# TouchMyHeart.net
KiCad netlist of a schematic drawn in Altium Designer
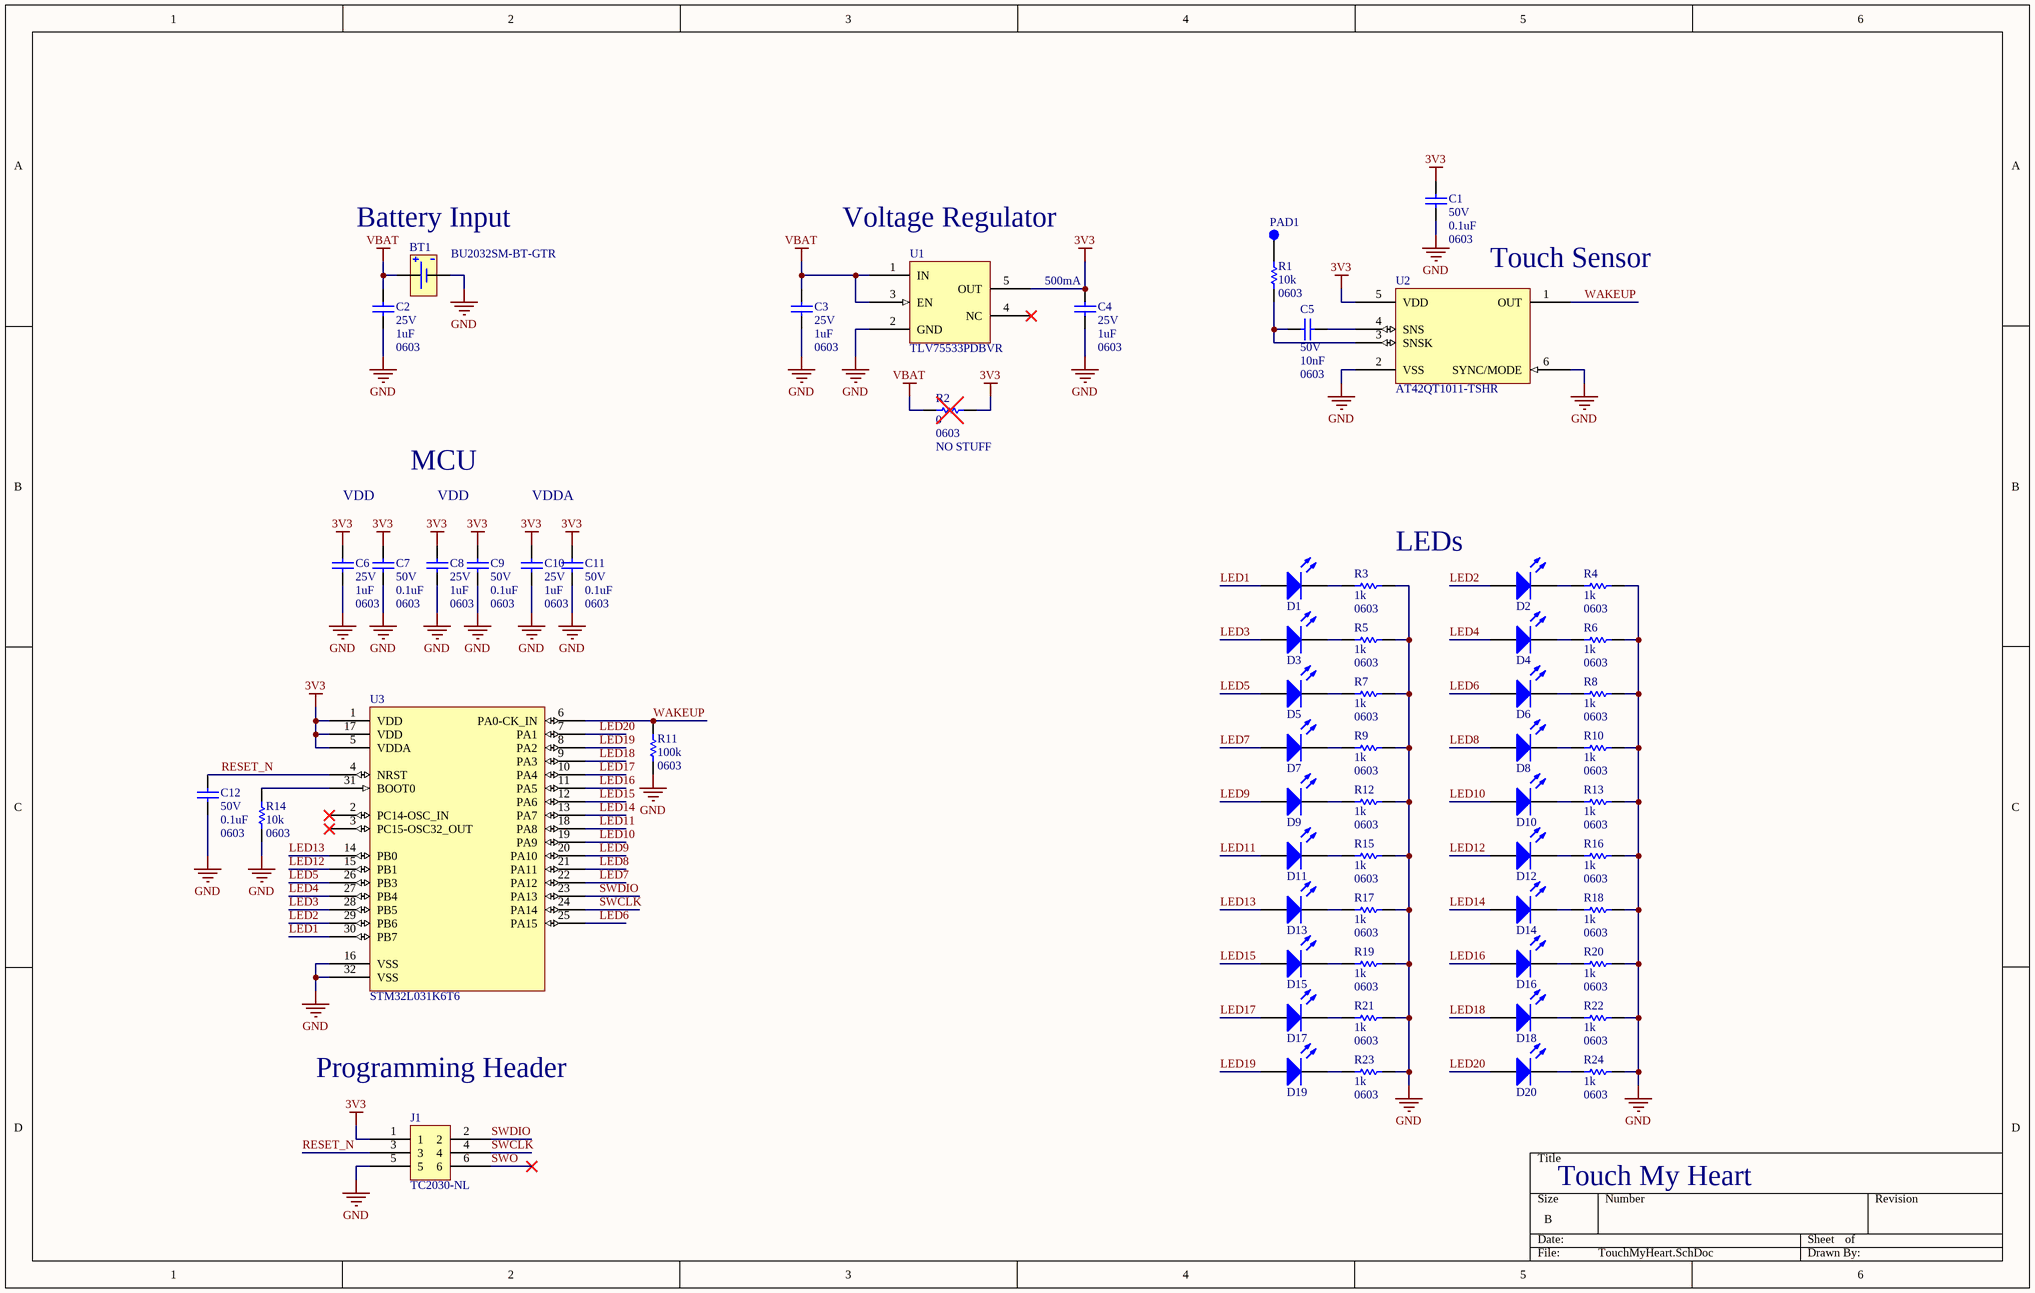
[diagram p0: TouchMyHeart.SchDoc]

(export (version "E")
  (design (tool "Eeschema 10.0.6"))
  (components
    (comp (ref "BT1")
      (value "BU2032SM-BT-GTR")
      (footprint "Footprint_Battery:BU2032SM-BT-GTR")
      (description "BATTERY HOLDER COIN 20MM SMD")
      (fields (field (name "MANUFACTURER") "Memory Protection Devices"))
      (libsource (lib "Schematic_Battery") (part "BU2032SM-BT-GTR"))
    )
    (comp (ref "C1")
      (value "0.1uF")
      (footprint "Footprint_Capacitor:CAPC1608X09N")
      (description "General purpose capacitor")
      (fields
        (field (name "RATED VOLTAGE") "50V")
        (field (name "PACKAGE") "0603")
        (field (name "Comment") "Capacitor")
      )
      (libsource (lib "Schematic_Generic") (part "Capacitor"))
    )
    (comp (ref "C2")
      (value "1uF")
      (footprint "Footprint_Capacitor:CAPC1608X09N")
      (description "General purpose capacitor")
      (fields
        (field (name "RATED VOLTAGE") "25V")
        (field (name "PACKAGE") "0603")
        (field (name "Comment") "Capacitor")
      )
      (libsource (lib "Schematic_Generic") (part "Capacitor"))
    )
    (comp (ref "C3")
      (value "1uF")
      (footprint "Footprint_Capacitor:CAPC1608X09N")
      (description "General purpose capacitor")
      (fields
        (field (name "RATED VOLTAGE") "25V")
        (field (name "PACKAGE") "0603")
        (field (name "Comment") "Capacitor")
      )
      (libsource (lib "Schematic_Generic") (part "Capacitor"))
    )
    (comp (ref "C4")
      (value "1uF")
      (footprint "Footprint_Capacitor:CAPC1608X09N")
      (description "General purpose capacitor")
      (fields
        (field (name "RATED VOLTAGE") "25V")
        (field (name "PACKAGE") "0603")
        (field (name "Comment") "Capacitor")
      )
      (libsource (lib "Schematic_Generic") (part "Capacitor"))
    )
    (comp (ref "C5")
      (value "10nF")
      (footprint "Footprint_Capacitor:CAPC1608X09N")
      (description "General purpose capacitor")
      (fields
        (field (name "RATED VOLTAGE") "50V")
        (field (name "PACKAGE") "0603")
        (field (name "Comment") "Capacitor")
      )
      (libsource (lib "Schematic_Generic") (part "Capacitor"))
    )
    (comp (ref "C6")
      (value "1uF")
      (footprint "Footprint_Capacitor:CAPC1608X09N")
      (description "General purpose capacitor")
      (fields
        (field (name "RATED VOLTAGE") "25V")
        (field (name "PACKAGE") "0603")
        (field (name "Comment") "Capacitor")
      )
      (libsource (lib "Schematic_Generic") (part "Capacitor"))
    )
    (comp (ref "C7")
      (value "0.1uF")
      (footprint "Footprint_Capacitor:CAPC1608X09N")
      (description "General purpose capacitor")
      (fields
        (field (name "RATED VOLTAGE") "50V")
        (field (name "PACKAGE") "0603")
        (field (name "Comment") "Capacitor")
      )
      (libsource (lib "Schematic_Generic") (part "Capacitor"))
    )
    (comp (ref "C8")
      (value "1uF")
      (footprint "Footprint_Capacitor:CAPC1608X09N")
      (description "General purpose capacitor")
      (fields
        (field (name "RATED VOLTAGE") "25V")
        (field (name "PACKAGE") "0603")
        (field (name "Comment") "Capacitor")
      )
      (libsource (lib "Schematic_Generic") (part "Capacitor"))
    )
    (comp (ref "C9")
      (value "0.1uF")
      (footprint "Footprint_Capacitor:CAPC1608X09N")
      (description "General purpose capacitor")
      (fields
        (field (name "RATED VOLTAGE") "50V")
        (field (name "PACKAGE") "0603")
        (field (name "Comment") "Capacitor")
      )
      (libsource (lib "Schematic_Generic") (part "Capacitor"))
    )
    (comp (ref "C10")
      (value "1uF")
      (footprint "Footprint_Capacitor:CAPC1608X09N")
      (description "General purpose capacitor")
      (fields
        (field (name "RATED VOLTAGE") "25V")
        (field (name "PACKAGE") "0603")
        (field (name "Comment") "Capacitor")
      )
      (libsource (lib "Schematic_Generic") (part "Capacitor"))
    )
    (comp (ref "C11")
      (value "0.1uF")
      (footprint "Footprint_Capacitor:CAPC1608X09N")
      (description "General purpose capacitor")
      (fields
        (field (name "RATED VOLTAGE") "50V")
        (field (name "PACKAGE") "0603")
        (field (name "Comment") "Capacitor")
      )
      (libsource (lib "Schematic_Generic") (part "Capacitor"))
    )
    (comp (ref "C12")
      (value "0.1uF")
      (footprint "Footprint_Capacitor:CAPC1608X09N")
      (description "General purpose capacitor")
      (fields
        (field (name "RATED VOLTAGE") "50V")
        (field (name "PACKAGE") "0603")
        (field (name "Comment") "Capacitor")
      )
      (libsource (lib "Schematic_Generic") (part "Capacitor"))
    )
    (comp (ref "D1")
      (value "LED")
      (footprint "Footprint_LED:DIOC3216X11N")
      (description "General purpose LED")
      (libsource (lib "Schematic_Generic") (part "LED"))
    )
    (comp (ref "D2")
      (value "LED")
      (footprint "Footprint_LED:DIOC3216X11N")
      (description "General purpose LED")
      (libsource (lib "Schematic_Generic") (part "LED"))
    )
    (comp (ref "D3")
      (value "LED")
      (footprint "Footprint_LED:DIOC3216X11N")
      (description "General purpose LED")
      (libsource (lib "Schematic_Generic") (part "LED"))
    )
    (comp (ref "D4")
      (value "LED")
      (footprint "Footprint_LED:DIOC3216X11N")
      (description "General purpose LED")
      (libsource (lib "Schematic_Generic") (part "LED"))
    )
    (comp (ref "D5")
      (value "LED")
      (footprint "Footprint_LED:DIOC3216X11N")
      (description "General purpose LED")
      (libsource (lib "Schematic_Generic") (part "LED"))
    )
    (comp (ref "D6")
      (value "LED")
      (footprint "Footprint_LED:DIOC3216X11N")
      (description "General purpose LED")
      (libsource (lib "Schematic_Generic") (part "LED"))
    )
    (comp (ref "D7")
      (value "LED")
      (footprint "Footprint_LED:DIOC3216X11N")
      (description "General purpose LED")
      (libsource (lib "Schematic_Generic") (part "LED"))
    )
    (comp (ref "D8")
      (value "LED")
      (footprint "Footprint_LED:DIOC3216X11N")
      (description "General purpose LED")
      (libsource (lib "Schematic_Generic") (part "LED"))
    )
    (comp (ref "D9")
      (value "LED")
      (footprint "Footprint_LED:DIOC3216X11N")
      (description "General purpose LED")
      (libsource (lib "Schematic_Generic") (part "LED"))
    )
    (comp (ref "D10")
      (value "LED")
      (footprint "Footprint_LED:DIOC3216X11N")
      (description "General purpose LED")
      (libsource (lib "Schematic_Generic") (part "LED"))
    )
    (comp (ref "D11")
      (value "LED")
      (footprint "Footprint_LED:DIOC3216X11N")
      (description "General purpose LED")
      (libsource (lib "Schematic_Generic") (part "LED"))
    )
    (comp (ref "D12")
      (value "LED")
      (footprint "Footprint_LED:DIOC3216X11N")
      (description "General purpose LED")
      (libsource (lib "Schematic_Generic") (part "LED"))
    )
    (comp (ref "D13")
      (value "LED")
      (footprint "Footprint_LED:DIOC3216X11N")
      (description "General purpose LED")
      (libsource (lib "Schematic_Generic") (part "LED"))
    )
    (comp (ref "D14")
      (value "LED")
      (footprint "Footprint_LED:DIOC3216X11N")
      (description "General purpose LED")
      (libsource (lib "Schematic_Generic") (part "LED"))
    )
    (comp (ref "D15")
      (value "LED")
      (footprint "Footprint_LED:DIOC3216X11N")
      (description "General purpose LED")
      (libsource (lib "Schematic_Generic") (part "LED"))
    )
    (comp (ref "D16")
      (value "LED")
      (footprint "Footprint_LED:DIOC3216X11N")
      (description "General purpose LED")
      (libsource (lib "Schematic_Generic") (part "LED"))
    )
    (comp (ref "D17")
      (value "LED")
      (footprint "Footprint_LED:DIOC3216X11N")
      (description "General purpose LED")
      (libsource (lib "Schematic_Generic") (part "LED"))
    )
    (comp (ref "D18")
      (value "LED")
      (footprint "Footprint_LED:DIOC3216X11N")
      (description "General purpose LED")
      (libsource (lib "Schematic_Generic") (part "LED"))
    )
    (comp (ref "D19")
      (value "LED")
      (footprint "Footprint_LED:DIOC3216X11N")
      (description "General purpose LED")
      (libsource (lib "Schematic_Generic") (part "LED"))
    )
    (comp (ref "D20")
      (value "LED")
      (footprint "Footprint_LED:DIOC3216X11N")
      (description "General purpose LED")
      (libsource (lib "Schematic_Generic") (part "LED"))
    )
    (comp (ref "J1")
      (value "TC2030-NL")
      (footprint "Footprint_Connector:TC2030-NL")
      (description "6-Pin No-Legs Tag-Connect Plug-of-Nails™ Cable with Ribbon Connector")
      (libsource (lib "Schematic_Connector") (part "TC2030-NL"))
    )
    (comp (ref "PAD1")
      (value "~")
      (footprint "Footprint_Button:CAPACTIVE_TOUCH")
      (description "Capacitive Touch Button")
      (libsource (lib "Schematic_Button") (part "CAPACITIVE_TOUCH"))
    )
    (comp (ref "R1")
      (value "10k")
      (footprint "Footprint_Resistor:RESC1608X06N")
      (description "General purpose resistor")
      (fields (field (name "PACKAGE") "0603") (field (name "Comment") "Resistor"))
      (libsource (lib "Schematic_Generic") (part "Resistor"))
    )
    (comp (ref "R2")
      (value "0")
      (footprint "Footprint_Resistor:RESC1608X06N")
      (description "General purpose resistor")
      (fields
        (field (name "PACKAGE") "0603")
        (field (name "NOTE") "NO STUFF")
        (field (name "Comment") "Resistor")
      )
      (libsource (lib "Schematic_Generic") (part "Resistor"))
    )
    (comp (ref "R3")
      (value "1k")
      (footprint "Footprint_Resistor:RESC1608X06N")
      (description "General purpose resistor")
      (fields (field (name "PACKAGE") "0603") (field (name "Comment") "Resistor"))
      (libsource (lib "Schematic_Generic") (part "Resistor"))
    )
    (comp (ref "R4")
      (value "1k")
      (footprint "Footprint_Resistor:RESC1608X06N")
      (description "General purpose resistor")
      (fields (field (name "PACKAGE") "0603") (field (name "Comment") "Resistor"))
      (libsource (lib "Schematic_Generic") (part "Resistor"))
    )
    (comp (ref "R5")
      (value "1k")
      (footprint "Footprint_Resistor:RESC1608X06N")
      (description "General purpose resistor")
      (fields (field (name "PACKAGE") "0603") (field (name "Comment") "Resistor"))
      (libsource (lib "Schematic_Generic") (part "Resistor"))
    )
    (comp (ref "R6")
      (value "1k")
      (footprint "Footprint_Resistor:RESC1608X06N")
      (description "General purpose resistor")
      (fields (field (name "PACKAGE") "0603") (field (name "Comment") "Resistor"))
      (libsource (lib "Schematic_Generic") (part "Resistor"))
    )
    (comp (ref "R7")
      (value "1k")
      (footprint "Footprint_Resistor:RESC1608X06N")
      (description "General purpose resistor")
      (fields (field (name "PACKAGE") "0603") (field (name "Comment") "Resistor"))
      (libsource (lib "Schematic_Generic") (part "Resistor"))
    )
    (comp (ref "R8")
      (value "1k")
      (footprint "Footprint_Resistor:RESC1608X06N")
      (description "General purpose resistor")
      (fields (field (name "PACKAGE") "0603") (field (name "Comment") "Resistor"))
      (libsource (lib "Schematic_Generic") (part "Resistor"))
    )
    (comp (ref "R9")
      (value "1k")
      (footprint "Footprint_Resistor:RESC1608X06N")
      (description "General purpose resistor")
      (fields (field (name "PACKAGE") "0603") (field (name "Comment") "Resistor"))
      (libsource (lib "Schematic_Generic") (part "Resistor"))
    )
    (comp (ref "R10")
      (value "1k")
      (footprint "Footprint_Resistor:RESC1608X06N")
      (description "General purpose resistor")
      (fields (field (name "PACKAGE") "0603") (field (name "Comment") "Resistor"))
      (libsource (lib "Schematic_Generic") (part "Resistor"))
    )
    (comp (ref "R11")
      (value "100k")
      (footprint "Footprint_Resistor:RESC1608X06N")
      (description "General purpose resistor")
      (fields (field (name "PACKAGE") "0603") (field (name "Comment") "Resistor"))
      (libsource (lib "Schematic_Generic") (part "Resistor"))
    )
    (comp (ref "R12")
      (value "1k")
      (footprint "Footprint_Resistor:RESC1608X06N")
      (description "General purpose resistor")
      (fields (field (name "PACKAGE") "0603") (field (name "Comment") "Resistor"))
      (libsource (lib "Schematic_Generic") (part "Resistor"))
    )
    (comp (ref "R13")
      (value "1k")
      (footprint "Footprint_Resistor:RESC1608X06N")
      (description "General purpose resistor")
      (fields (field (name "PACKAGE") "0603") (field (name "Comment") "Resistor"))
      (libsource (lib "Schematic_Generic") (part "Resistor"))
    )
    (comp (ref "R14")
      (value "10k")
      (footprint "Footprint_Resistor:RESC1608X06N")
      (description "General purpose resistor")
      (fields (field (name "PACKAGE") "0603") (field (name "Comment") "Resistor"))
      (libsource (lib "Schematic_Generic") (part "Resistor"))
    )
    (comp (ref "R15")
      (value "1k")
      (footprint "Footprint_Resistor:RESC1608X06N")
      (description "General purpose resistor")
      (fields (field (name "PACKAGE") "0603") (field (name "Comment") "Resistor"))
      (libsource (lib "Schematic_Generic") (part "Resistor"))
    )
    (comp (ref "R16")
      (value "1k")
      (footprint "Footprint_Resistor:RESC1608X06N")
      (description "General purpose resistor")
      (fields (field (name "PACKAGE") "0603") (field (name "Comment") "Resistor"))
      (libsource (lib "Schematic_Generic") (part "Resistor"))
    )
    (comp (ref "R17")
      (value "1k")
      (footprint "Footprint_Resistor:RESC1608X06N")
      (description "General purpose resistor")
      (fields (field (name "PACKAGE") "0603") (field (name "Comment") "Resistor"))
      (libsource (lib "Schematic_Generic") (part "Resistor"))
    )
    (comp (ref "R18")
      (value "1k")
      (footprint "Footprint_Resistor:RESC1608X06N")
      (description "General purpose resistor")
      (fields (field (name "PACKAGE") "0603") (field (name "Comment") "Resistor"))
      (libsource (lib "Schematic_Generic") (part "Resistor"))
    )
    (comp (ref "R19")
      (value "1k")
      (footprint "Footprint_Resistor:RESC1608X06N")
      (description "General purpose resistor")
      (fields (field (name "PACKAGE") "0603") (field (name "Comment") "Resistor"))
      (libsource (lib "Schematic_Generic") (part "Resistor"))
    )
    (comp (ref "R20")
      (value "1k")
      (footprint "Footprint_Resistor:RESC1608X06N")
      (description "General purpose resistor")
      (fields (field (name "PACKAGE") "0603") (field (name "Comment") "Resistor"))
      (libsource (lib "Schematic_Generic") (part "Resistor"))
    )
    (comp (ref "R21")
      (value "1k")
      (footprint "Footprint_Resistor:RESC1608X06N")
      (description "General purpose resistor")
      (fields (field (name "PACKAGE") "0603") (field (name "Comment") "Resistor"))
      (libsource (lib "Schematic_Generic") (part "Resistor"))
    )
    (comp (ref "R22")
      (value "1k")
      (footprint "Footprint_Resistor:RESC1608X06N")
      (description "General purpose resistor")
      (fields (field (name "PACKAGE") "0603") (field (name "Comment") "Resistor"))
      (libsource (lib "Schematic_Generic") (part "Resistor"))
    )
    (comp (ref "R23")
      (value "1k")
      (footprint "Footprint_Resistor:RESC1608X06N")
      (description "General purpose resistor")
      (fields (field (name "PACKAGE") "0603") (field (name "Comment") "Resistor"))
      (libsource (lib "Schematic_Generic") (part "Resistor"))
    )
    (comp (ref "R24")
      (value "1k")
      (footprint "Footprint_Resistor:RESC1608X06N")
      (description "General purpose resistor")
      (fields (field (name "PACKAGE") "0603") (field (name "Comment") "Resistor"))
      (libsource (lib "Schematic_Generic") (part "Resistor"))
    )
    (comp (ref "U1")
      (value "TLV75533PDBVR")
      (footprint "Footprint_PMIC:SOT95P280X145-5N")
      (description "IC REG LINEAR 3.3V 500MA SOT23-5")
      (fields (field (name "MANUFACTURER") "Texas Instruments"))
      (libsource (lib "Schematic_PMIC") (part "TLV75533PDBVR"))
    )
    (comp (ref "U2")
      (value "AT42QT1011-TSHR")
      (footprint "Footprint_IC:SOT95P280X145-6N")
      (description "Touch Sensor IC 6-Pin SOT-23, HOLD")
      (fields (field (name "MANUFACTURER") "Microchip / Atmel"))
      (libsource (lib "Schematic_IC") (part "AT42QT1011-TSHR"))
    )
    (comp (ref "U3")
      (value "STM32L031K6T6")
      (footprint "Footprint_MCU:TQFP80P900X900X160-32N")
      (description "IC MCU 32BIT 32KB FLASH 32LQFP")
      (fields (field (name "MANUFACTURER") "STMicroelectronics"))
      (libsource (lib "Schematic_MCU") (part "STM32L031K6T6"))
    )
  )
  (nets
    (net (code "1") (name "/LED1") (class "Default")
      (node (ref "D1") (pin "1") (pinfunction "A_1") (pintype "passive"))
      (node (ref "U3") (pin "30") (pinfunction "PB7_30") (pintype "bidirectional"))
    )
    (net (code "2") (name "/LED2") (class "Default")
      (node (ref "D2") (pin "1") (pinfunction "A_1") (pintype "passive"))
      (node (ref "U3") (pin "29") (pinfunction "PB6_29") (pintype "bidirectional"))
    )
    (net (code "3") (name "/LED3") (class "Default")
      (node (ref "D3") (pin "1") (pinfunction "A_1") (pintype "passive"))
      (node (ref "U3") (pin "28") (pinfunction "PB5_28") (pintype "bidirectional"))
    )
    (net (code "4") (name "/LED4") (class "Default")
      (node (ref "D4") (pin "1") (pinfunction "A_1") (pintype "passive"))
      (node (ref "U3") (pin "27") (pinfunction "PB4_27") (pintype "bidirectional"))
    )
    (net (code "5") (name "/LED5") (class "Default")
      (node (ref "D5") (pin "1") (pinfunction "A_1") (pintype "passive"))
      (node (ref "U3") (pin "26") (pinfunction "PB3_26") (pintype "bidirectional"))
    )
    (net (code "6") (name "/LED6") (class "Default")
      (node (ref "D6") (pin "1") (pinfunction "A_1") (pintype "passive"))
      (node (ref "U3") (pin "25") (pinfunction "PA15_25") (pintype "bidirectional"))
    )
    (net (code "7") (name "/LED7") (class "Default")
      (node (ref "D7") (pin "1") (pinfunction "A_1") (pintype "passive"))
      (node (ref "U3") (pin "22") (pinfunction "PA12_22") (pintype "bidirectional"))
    )
    (net (code "8") (name "/LED8") (class "Default")
      (node (ref "D8") (pin "1") (pinfunction "A_1") (pintype "passive"))
      (node (ref "U3") (pin "21") (pinfunction "PA11_21") (pintype "bidirectional"))
    )
    (net (code "9") (name "/LED9") (class "Default")
      (node (ref "D9") (pin "1") (pinfunction "A_1") (pintype "passive"))
      (node (ref "U3") (pin "20") (pinfunction "PA10_20") (pintype "bidirectional"))
    )
    (net (code "10") (name "/LED10") (class "Default")
      (node (ref "D10") (pin "1") (pinfunction "A_1") (pintype "passive"))
      (node (ref "U3") (pin "19") (pinfunction "PA9_19") (pintype "bidirectional"))
    )
    (net (code "11") (name "/LED11") (class "Default")
      (node (ref "D11") (pin "1") (pinfunction "A_1") (pintype "passive"))
      (node (ref "U3") (pin "18") (pinfunction "PA8_18") (pintype "bidirectional"))
    )
    (net (code "12") (name "/LED12") (class "Default")
      (node (ref "D12") (pin "1") (pinfunction "A_1") (pintype "passive"))
      (node (ref "U3") (pin "15") (pinfunction "PB1_15") (pintype "bidirectional"))
    )
    (net (code "13") (name "/LED13") (class "Default")
      (node (ref "D13") (pin "1") (pinfunction "A_1") (pintype "passive"))
      (node (ref "U3") (pin "14") (pinfunction "PB0_14") (pintype "bidirectional"))
    )
    (net (code "14") (name "/LED14") (class "Default")
      (node (ref "D14") (pin "1") (pinfunction "A_1") (pintype "passive"))
      (node (ref "U3") (pin "13") (pinfunction "PA7_13") (pintype "bidirectional"))
    )
    (net (code "15") (name "/LED15") (class "Default")
      (node (ref "D15") (pin "1") (pinfunction "A_1") (pintype "passive"))
      (node (ref "U3") (pin "12") (pinfunction "PA6_12") (pintype "bidirectional"))
    )
    (net (code "16") (name "/LED16") (class "Default")
      (node (ref "D16") (pin "1") (pinfunction "A_1") (pintype "passive"))
      (node (ref "U3") (pin "11") (pinfunction "PA5_11") (pintype "bidirectional"))
    )
    (net (code "17") (name "/LED17") (class "Default")
      (node (ref "D17") (pin "1") (pinfunction "A_1") (pintype "passive"))
      (node (ref "U3") (pin "10") (pinfunction "PA4_10") (pintype "bidirectional"))
    )
    (net (code "18") (name "/LED18") (class "Default")
      (node (ref "D18") (pin "1") (pinfunction "A_1") (pintype "passive"))
      (node (ref "U3") (pin "9") (pinfunction "PA3_9") (pintype "bidirectional"))
    )
    (net (code "19") (name "/LED19") (class "Default")
      (node (ref "D19") (pin "1") (pinfunction "A_1") (pintype "passive"))
      (node (ref "U3") (pin "8") (pinfunction "PA2_8") (pintype "bidirectional"))
    )
    (net (code "20") (name "/LED20") (class "Default")
      (node (ref "D20") (pin "1") (pinfunction "A_1") (pintype "passive"))
      (node (ref "U3") (pin "7") (pinfunction "PA1_7") (pintype "bidirectional"))
    )
    (net (code "21") (name "/RESET_N") (class "Default")
      (node (ref "C12") (pin "2") (pinfunction "2_2") (pintype "passive"))
      (node (ref "J1") (pin "3") (pinfunction "3_3") (pintype "passive"))
      (node (ref "U3") (pin "4") (pinfunction "NRST_4") (pintype "bidirectional"))
    )
    (net (code "22") (name "/SWCLK") (class "Default")
      (node (ref "J1") (pin "4") (pinfunction "4_4") (pintype "passive"))
      (node (ref "U3") (pin "24") (pinfunction "PA14_24") (pintype "bidirectional"))
    )
    (net (code "23") (name "/SWDIO") (class "Default")
      (node (ref "J1") (pin "2") (pinfunction "2_2") (pintype "passive"))
      (node (ref "U3") (pin "23") (pinfunction "PA13_23") (pintype "bidirectional"))
    )
    (net (code "24") (name "/SWO") (class "Default")
      (node (ref "J1") (pin "6") (pinfunction "6_6") (pintype "passive+no_connect"))
    )
    (net (code "25") (name "/WAKEUP") (class "Default")
      (node (ref "R11") (pin "2") (pinfunction "2_2") (pintype "passive"))
      (node (ref "U2") (pin "1") (pinfunction "OUT_1") (pintype "power_in"))
      (node (ref "U3") (pin "6") (pinfunction "PA0-CK_IN_6") (pintype "bidirectional"))
    )
    (net (code "26") (name "3V3") (class "Default")
      (node (ref "C1") (pin "2") (pinfunction "2_2") (pintype "passive"))
      (node (ref "C10") (pin "2") (pinfunction "2_2") (pintype "passive"))
      (node (ref "C11") (pin "2") (pinfunction "2_2") (pintype "passive"))
      (node (ref "C4") (pin "2") (pinfunction "2_2") (pintype "passive"))
      (node (ref "C6") (pin "2") (pinfunction "2_2") (pintype "passive"))
      (node (ref "C7") (pin "2") (pinfunction "2_2") (pintype "passive"))
      (node (ref "C8") (pin "2") (pinfunction "2_2") (pintype "passive"))
      (node (ref "C9") (pin "2") (pinfunction "2_2") (pintype "passive"))
      (node (ref "J1") (pin "1") (pinfunction "1_1") (pintype "passive"))
      (node (ref "R2") (pin "1") (pinfunction "1_1") (pintype "passive"))
      (node (ref "U1") (pin "5") (pinfunction "OUT_5") (pintype "power_in"))
      (node (ref "U2") (pin "5") (pinfunction "VDD_5") (pintype "power_in"))
      (node (ref "U3") (pin "1") (pinfunction "VDD_1") (pintype "power_in"))
      (node (ref "U3") (pin "17") (pinfunction "VDD_17") (pintype "power_in"))
      (node (ref "U3") (pin "5") (pinfunction "VDDA_5") (pintype "power_in"))
    )
    (net (code "27") (name "GND") (class "Default")
      (node (ref "BT1") (pin "B-") (pinfunction "B-_B-") (pintype "power_in"))
      (node (ref "C1") (pin "1") (pinfunction "1_1") (pintype "passive"))
      (node (ref "C10") (pin "1") (pinfunction "1_1") (pintype "passive"))
      (node (ref "C11") (pin "1") (pinfunction "1_1") (pintype "passive"))
      (node (ref "C12") (pin "1") (pinfunction "1_1") (pintype "passive"))
      (node (ref "C2") (pin "1") (pinfunction "1_1") (pintype "passive"))
      (node (ref "C3") (pin "1") (pinfunction "1_1") (pintype "passive"))
      (node (ref "C4") (pin "1") (pinfunction "1_1") (pintype "passive"))
      (node (ref "C6") (pin "1") (pinfunction "1_1") (pintype "passive"))
      (node (ref "C7") (pin "1") (pinfunction "1_1") (pintype "passive"))
      (node (ref "C8") (pin "1") (pinfunction "1_1") (pintype "passive"))
      (node (ref "C9") (pin "1") (pinfunction "1_1") (pintype "passive"))
      (node (ref "J1") (pin "5") (pinfunction "5_5") (pintype "passive"))
      (node (ref "R10") (pin "2") (pinfunction "2_2") (pintype "passive"))
      (node (ref "R11") (pin "1") (pinfunction "1_1") (pintype "passive"))
      (node (ref "R12") (pin "2") (pinfunction "2_2") (pintype "passive"))
      (node (ref "R13") (pin "2") (pinfunction "2_2") (pintype "passive"))
      (node (ref "R14") (pin "1") (pinfunction "1_1") (pintype "passive"))
      (node (ref "R15") (pin "2") (pinfunction "2_2") (pintype "passive"))
      (node (ref "R16") (pin "2") (pinfunction "2_2") (pintype "passive"))
      (node (ref "R17") (pin "2") (pinfunction "2_2") (pintype "passive"))
      (node (ref "R18") (pin "2") (pinfunction "2_2") (pintype "passive"))
      (node (ref "R19") (pin "2") (pinfunction "2_2") (pintype "passive"))
      (node (ref "R20") (pin "2") (pinfunction "2_2") (pintype "passive"))
      (node (ref "R21") (pin "2") (pinfunction "2_2") (pintype "passive"))
      (node (ref "R22") (pin "2") (pinfunction "2_2") (pintype "passive"))
      (node (ref "R23") (pin "2") (pinfunction "2_2") (pintype "passive"))
      (node (ref "R24") (pin "2") (pinfunction "2_2") (pintype "passive"))
      (node (ref "R3") (pin "2") (pinfunction "2_2") (pintype "passive"))
      (node (ref "R4") (pin "2") (pinfunction "2_2") (pintype "passive"))
      (node (ref "R5") (pin "2") (pinfunction "2_2") (pintype "passive"))
      (node (ref "R6") (pin "2") (pinfunction "2_2") (pintype "passive"))
      (node (ref "R7") (pin "2") (pinfunction "2_2") (pintype "passive"))
      (node (ref "R8") (pin "2") (pinfunction "2_2") (pintype "passive"))
      (node (ref "R9") (pin "2") (pinfunction "2_2") (pintype "passive"))
      (node (ref "U1") (pin "2") (pinfunction "GND_2") (pintype "power_in"))
      (node (ref "U2") (pin "2") (pinfunction "VSS_2") (pintype "power_in"))
      (node (ref "U2") (pin "6") (pinfunction "SYNC/MODE_6") (pintype "input"))
      (node (ref "U3") (pin "16") (pinfunction "VSS_16") (pintype "power_in"))
      (node (ref "U3") (pin "32") (pinfunction "VSS_32") (pintype "power_in"))
    )
    (net (code "28") (name "Net-(D1-K)") (class "Default")
      (node (ref "D1") (pin "2") (pinfunction "K_2") (pintype "passive"))
      (node (ref "R3") (pin "1") (pinfunction "1_1") (pintype "passive"))
    )
    (net (code "29") (name "Net-(D2-K)") (class "Default")
      (node (ref "D2") (pin "2") (pinfunction "K_2") (pintype "passive"))
      (node (ref "R4") (pin "1") (pinfunction "1_1") (pintype "passive"))
    )
    (net (code "30") (name "Net-(D3-K)") (class "Default")
      (node (ref "D3") (pin "2") (pinfunction "K_2") (pintype "passive"))
      (node (ref "R5") (pin "1") (pinfunction "1_1") (pintype "passive"))
    )
    (net (code "31") (name "Net-(D4-K)") (class "Default")
      (node (ref "D4") (pin "2") (pinfunction "K_2") (pintype "passive"))
      (node (ref "R6") (pin "1") (pinfunction "1_1") (pintype "passive"))
    )
    (net (code "32") (name "Net-(D5-K)") (class "Default")
      (node (ref "D5") (pin "2") (pinfunction "K_2") (pintype "passive"))
      (node (ref "R7") (pin "1") (pinfunction "1_1") (pintype "passive"))
    )
    (net (code "33") (name "Net-(D6-K)") (class "Default")
      (node (ref "D6") (pin "2") (pinfunction "K_2") (pintype "passive"))
      (node (ref "R8") (pin "1") (pinfunction "1_1") (pintype "passive"))
    )
    (net (code "34") (name "Net-(D7-K)") (class "Default")
      (node (ref "D7") (pin "2") (pinfunction "K_2") (pintype "passive"))
      (node (ref "R9") (pin "1") (pinfunction "1_1") (pintype "passive"))
    )
    (net (code "35") (name "Net-(D8-K)") (class "Default")
      (node (ref "D8") (pin "2") (pinfunction "K_2") (pintype "passive"))
      (node (ref "R10") (pin "1") (pinfunction "1_1") (pintype "passive"))
    )
    (net (code "36") (name "Net-(D9-K)") (class "Default")
      (node (ref "D9") (pin "2") (pinfunction "K_2") (pintype "passive"))
      (node (ref "R12") (pin "1") (pinfunction "1_1") (pintype "passive"))
    )
    (net (code "37") (name "Net-(D10-K)") (class "Default")
      (node (ref "D10") (pin "2") (pinfunction "K_2") (pintype "passive"))
      (node (ref "R13") (pin "1") (pinfunction "1_1") (pintype "passive"))
    )
    (net (code "38") (name "Net-(D11-K)") (class "Default")
      (node (ref "D11") (pin "2") (pinfunction "K_2") (pintype "passive"))
      (node (ref "R15") (pin "1") (pinfunction "1_1") (pintype "passive"))
    )
    (net (code "39") (name "Net-(D12-K)") (class "Default")
      (node (ref "D12") (pin "2") (pinfunction "K_2") (pintype "passive"))
      (node (ref "R16") (pin "1") (pinfunction "1_1") (pintype "passive"))
    )
    (net (code "40") (name "Net-(D13-K)") (class "Default")
      (node (ref "D13") (pin "2") (pinfunction "K_2") (pintype "passive"))
      (node (ref "R17") (pin "1") (pinfunction "1_1") (pintype "passive"))
    )
    (net (code "41") (name "Net-(D14-K)") (class "Default")
      (node (ref "D14") (pin "2") (pinfunction "K_2") (pintype "passive"))
      (node (ref "R18") (pin "1") (pinfunction "1_1") (pintype "passive"))
    )
    (net (code "42") (name "Net-(D15-K)") (class "Default")
      (node (ref "D15") (pin "2") (pinfunction "K_2") (pintype "passive"))
      (node (ref "R19") (pin "1") (pinfunction "1_1") (pintype "passive"))
    )
    (net (code "43") (name "Net-(D16-K)") (class "Default")
      (node (ref "D16") (pin "2") (pinfunction "K_2") (pintype "passive"))
      (node (ref "R20") (pin "1") (pinfunction "1_1") (pintype "passive"))
    )
    (net (code "44") (name "Net-(D17-K)") (class "Default")
      (node (ref "D17") (pin "2") (pinfunction "K_2") (pintype "passive"))
      (node (ref "R21") (pin "1") (pinfunction "1_1") (pintype "passive"))
    )
    (net (code "45") (name "Net-(D18-K)") (class "Default")
      (node (ref "D18") (pin "2") (pinfunction "K_2") (pintype "passive"))
      (node (ref "R22") (pin "1") (pinfunction "1_1") (pintype "passive"))
    )
    (net (code "46") (name "Net-(D19-K)") (class "Default")
      (node (ref "D19") (pin "2") (pinfunction "K_2") (pintype "passive"))
      (node (ref "R23") (pin "1") (pinfunction "1_1") (pintype "passive"))
    )
    (net (code "47") (name "Net-(D20-K)") (class "Default")
      (node (ref "D20") (pin "2") (pinfunction "K_2") (pintype "passive"))
      (node (ref "R24") (pin "1") (pinfunction "1_1") (pintype "passive"))
    )
    (net (code "48") (name "Net-(PAD1-Pad1)") (class "Default")
      (node (ref "PAD1") (pin "1") (pintype "passive"))
      (node (ref "R1") (pin "1") (pinfunction "1_1") (pintype "passive"))
    )
    (net (code "49") (name "Net-(U2-SNS)") (class "Default")
      (node (ref "C5") (pin "1") (pinfunction "1_1") (pintype "passive"))
      (node (ref "U2") (pin "4") (pinfunction "SNS_4") (pintype "bidirectional"))
    )
    (net (code "50") (name "Net-(U2-SNSK)") (class "Default")
      (node (ref "C5") (pin "2") (pinfunction "2_2") (pintype "passive"))
      (node (ref "R1") (pin "2") (pinfunction "2_2") (pintype "passive"))
      (node (ref "U2") (pin "3") (pinfunction "SNSK_3") (pintype "bidirectional"))
    )
    (net (code "51") (name "Net-(U3-BOOT0)") (class "Default")
      (node (ref "R14") (pin "2") (pinfunction "2_2") (pintype "passive"))
      (node (ref "U3") (pin "31") (pinfunction "BOOT0_31") (pintype "input"))
    )
    (net (code "52") (name "VBAT") (class "Default")
      (node (ref "BT1") (pin "B+") (pinfunction "B+_B+") (pintype "power_in"))
      (node (ref "C2") (pin "2") (pinfunction "2_2") (pintype "passive"))
      (node (ref "C3") (pin "2") (pinfunction "2_2") (pintype "passive"))
      (node (ref "R2") (pin "2") (pinfunction "2_2") (pintype "passive"))
      (node (ref "U1") (pin "1") (pinfunction "IN_1") (pintype "power_in"))
      (node (ref "U1") (pin "3") (pinfunction "EN_3") (pintype "input"))
    )
    (net (code "53") (name "unconnected-(U1-NC-Pad4)") (class "Default")
      (node (ref "U1") (pin "4") (pinfunction "NC_4") (pintype "passive+no_connect"))
    )
    (net (code "54") (name "unconnected-(U3-PC14-OSC_IN-Pad2)") (class "Default")
      (node (ref "U3") (pin "2") (pinfunction "PC14-OSC_IN_2") (pintype "bidirectional+no_connect"))
    )
    (net (code "55") (name "unconnected-(U3-PC15-OSC32_OUT-Pad3)") (class "Default")
      (node (ref "U3") (pin "3") (pinfunction "PC15-OSC32_OUT_3") (pintype "bidirectional+no_connect"))
    )
  )
)
